# ReflowOvenController.net
KiCad netlist of a schematic drawn in EAGLE
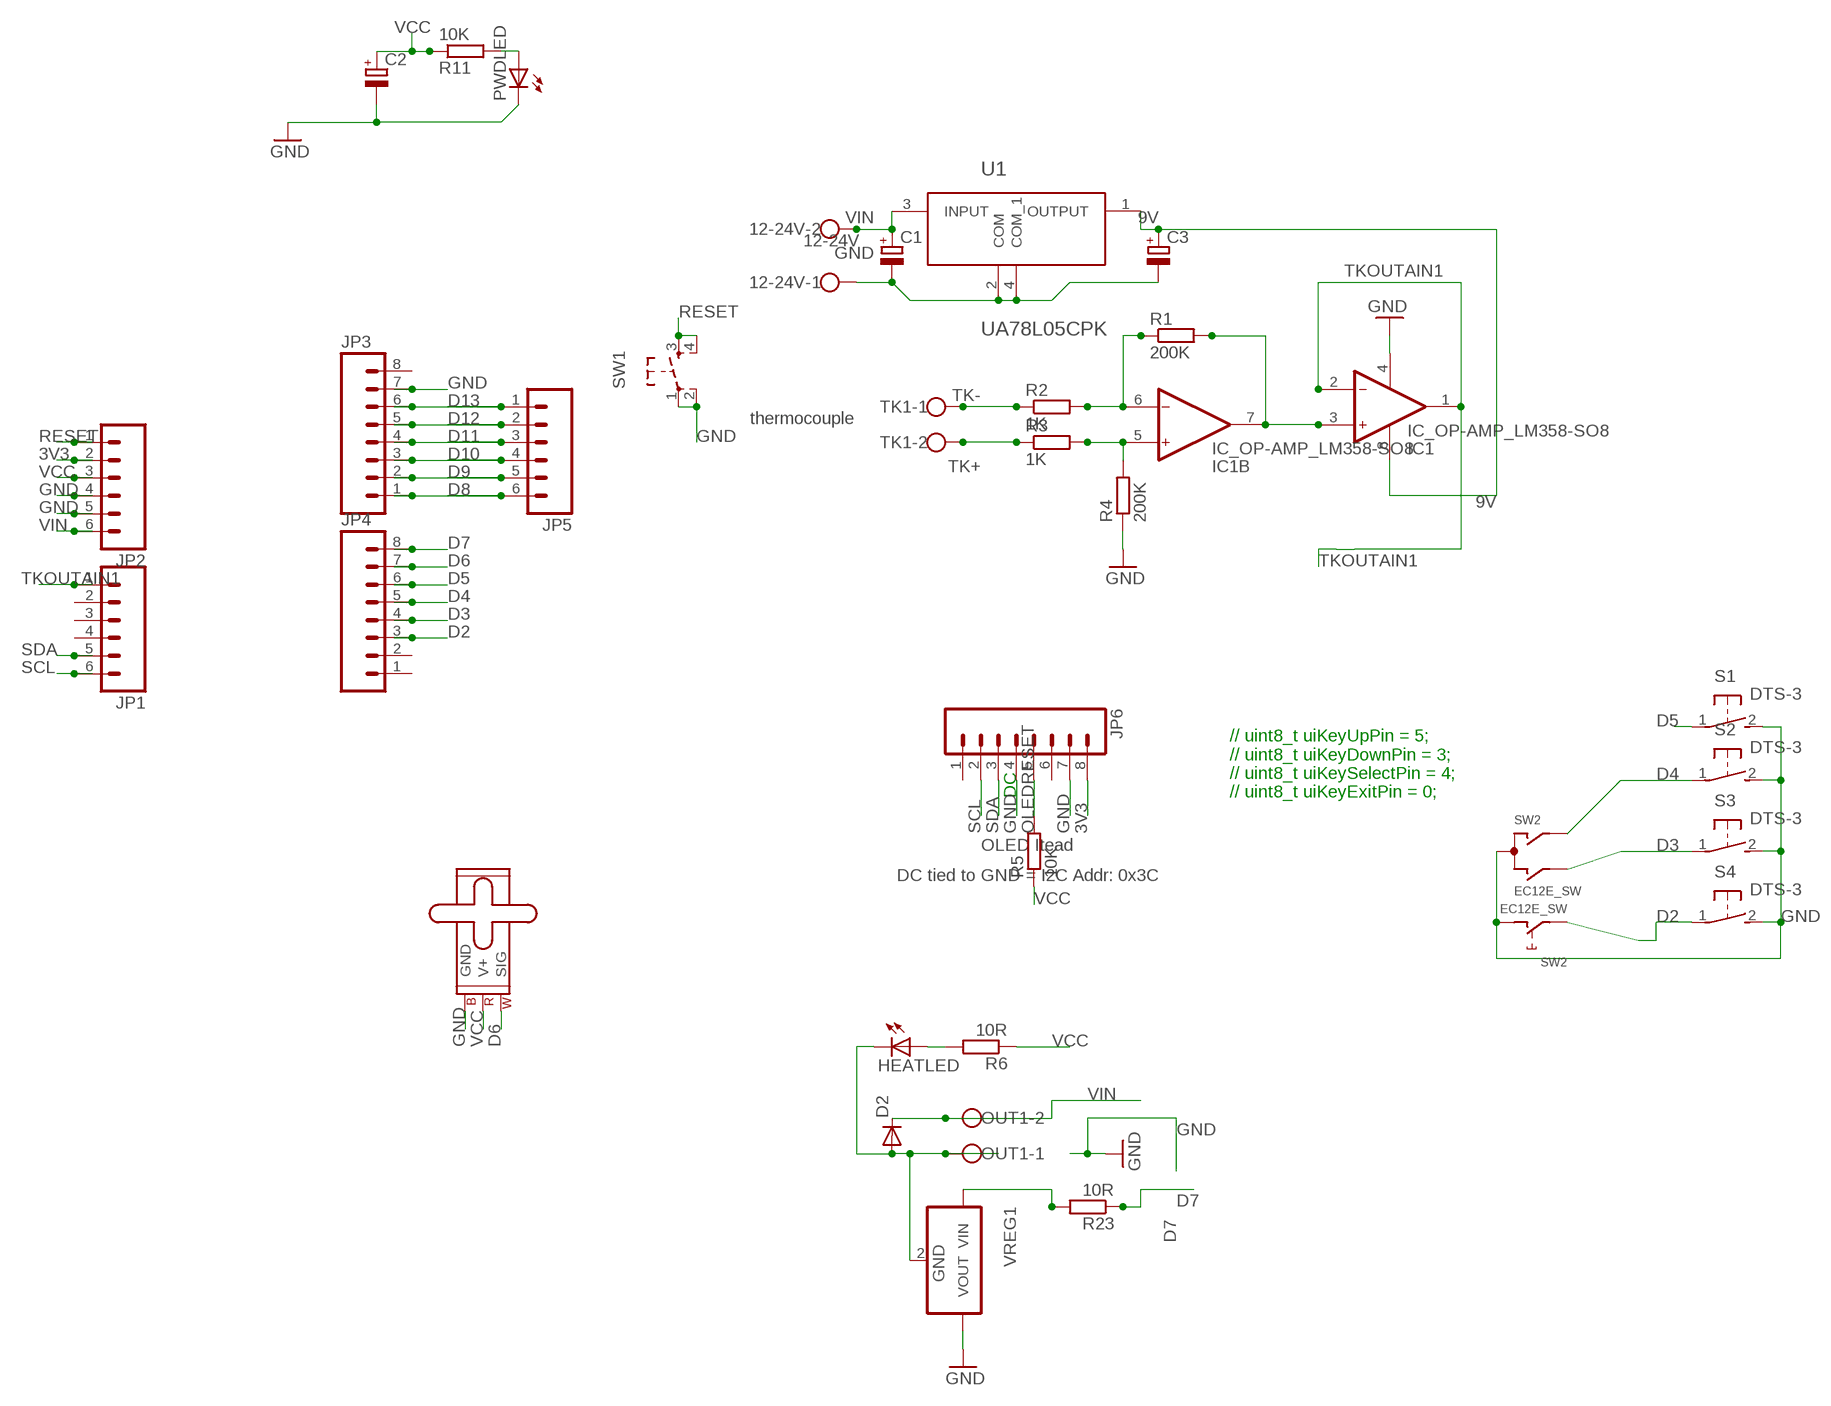
[diagram p0: schematic, sheet 1]

(export (version "E")
  (design (tool "Eeschema 10.0.6"))
  (components
    (comp (ref "12-24V")
      (value "W237-102")
      (footprint "eagle-import:W237-102")
      (fields (field (name "MPN") "237-102"))
      (libsource (lib "eagle-import") (part "W237-102"))
    )
    (comp (ref "C1")
      (value "CPOL-EU153CLV-0505")
      (footprint "eagle-import:153CLV-0505")
      (libsource (lib "eagle-import") (part "CPOL-EU153CLV-0505"))
    )
    (comp (ref "C2")
      (value "CPOL-EU153CLV-0505")
      (footprint "eagle-import:153CLV-0505")
      (libsource (lib "eagle-import") (part "CPOL-EU153CLV-0505"))
    )
    (comp (ref "C3")
      (value "CPOL-EU153CLV-0505")
      (footprint "eagle-import:153CLV-0505")
      (libsource (lib "eagle-import") (part "CPOL-EU153CLV-0505"))
    )
    (comp (ref "D2")
      (value "DIODESMA-ALT")
      (footprint "eagle-import:SMA-DIODE_ALT")
      (libsource (lib "eagle-import") (part "DIODESMA-ALT"))
    )
    (comp (ref "HEATLED")
      (value "LEDCHIPLED_1206")
      (footprint "eagle-import:CHIPLED_1206")
      (libsource (lib "eagle-import") (part "LEDCHIPLED_1206"))
    )
    (comp (ref "IC1")
      (value "IC_OP-AMP_LM358-SO8")
      (footprint "eagle-import:SO-8")
      (libsource (lib "eagle-import") (part "IC_OP-AMP_LM358-SO8"))
    )
    (comp (ref "JP1")
      (value "M06LOCK_LONGPADS")
      (footprint "eagle-import:1X06_LOCK_LONGPADS")
      (libsource (lib "eagle-import") (part "M06LOCK_LONGPADS"))
    )
    (comp (ref "JP2")
      (value "M06LOCK_LONGPADS")
      (footprint "eagle-import:1X06_LOCK_LONGPADS")
      (libsource (lib "eagle-import") (part "M06LOCK_LONGPADS"))
    )
    (comp (ref "JP3")
      (value "M08LOCK_LONGPADS")
      (footprint "eagle-import:1X08_LOCK_LONGPADS")
      (libsource (lib "eagle-import") (part "M08LOCK_LONGPADS"))
    )
    (comp (ref "JP4")
      (value "M08LOCK_LONGPADS")
      (footprint "eagle-import:1X08_LOCK_LONGPADS")
      (libsource (lib "eagle-import") (part "M08LOCK_LONGPADS"))
    )
    (comp (ref "JP5")
      (value "M06LOCK_LONGPADS")
      (footprint "eagle-import:1X06_LOCK_LONGPADS")
      (libsource (lib "eagle-import") (part "M06LOCK_LONGPADS"))
    )
    (comp (ref "JP6")
      (value "M08LOCK")
      (footprint "eagle-import:1X08_LOCK")
      (libsource (lib "eagle-import") (part "M08LOCK"))
    )
    (comp (ref "OUT1")
      (value "W237-102")
      (footprint "eagle-import:W237-102")
      (fields (field (name "MPN") "237-102"))
      (libsource (lib "eagle-import") (part "W237-102"))
    )
    (comp (ref "PWDLED")
      (value "LEDCHIPLED_1206")
      (footprint "eagle-import:CHIPLED_1206")
      (libsource (lib "eagle-import") (part "LEDCHIPLED_1206"))
    )
    (comp (ref "R1")
      (value "200K")
      (footprint "eagle-import:M1206")
      (libsource (lib "eagle-import") (part "R-EU_M1206"))
    )
    (comp (ref "R2")
      (value "1K")
      (footprint "eagle-import:M1206")
      (libsource (lib "eagle-import") (part "R-EU_M1206"))
    )
    (comp (ref "R3")
      (value "1K")
      (footprint "eagle-import:M1206")
      (libsource (lib "eagle-import") (part "R-EU_M1206"))
    )
    (comp (ref "R4")
      (value "200K")
      (footprint "eagle-import:M1206")
      (libsource (lib "eagle-import") (part "R-EU_M1206"))
    )
    (comp (ref "R5")
      (value "10K")
      (footprint "eagle-import:R1206")
      (libsource (lib "eagle-import") (part "RESISTOR-1206"))
    )
    (comp (ref "R6")
      (value "10R")
      (footprint "eagle-import:M1206")
      (libsource (lib "eagle-import") (part "R-EU_M1206"))
    )
    (comp (ref "R11")
      (value "10K")
      (footprint "eagle-import:R1206")
      (libsource (lib "eagle-import") (part "RESISTOR-1206"))
    )
    (comp (ref "R23")
      (value "10R")
      (footprint "eagle-import:M1206")
      (libsource (lib "eagle-import") (part "R-EU_M1206"))
    )
    (comp (ref "S1")
      (value "DTS-3")
      (footprint "eagle-import:DTS-3")
      (libsource (lib "eagle-import") (part "DTS-3"))
    )
    (comp (ref "S2")
      (value "DTS-3")
      (footprint "eagle-import:DTS-3")
      (libsource (lib "eagle-import") (part "DTS-3"))
    )
    (comp (ref "S3")
      (value "DTS-3")
      (footprint "eagle-import:DTS-3")
      (libsource (lib "eagle-import") (part "DTS-3"))
    )
    (comp (ref "S4")
      (value "DTS-3")
      (footprint "eagle-import:DTS-3")
      (libsource (lib "eagle-import") (part "DTS-3"))
    )
    (comp (ref "SERVO")
      (value "SMALL_SERVO")
      (footprint "eagle-import:1X03")
      (libsource (lib "eagle-import") (part "SMALL_SERVO"))
    )
    (comp (ref "SW1")
      (value "SW_TACT_4P")
      (footprint "eagle-import:SW_TACT_SMALL")
      (libsource (lib "eagle-import") (part "SW_TACT_4P"))
    )
    (comp (ref "SW2")
      (value "EC12E_SW")
      (footprint "eagle-import:ALPS_EC12E_SW")
      (fields (field (name "MPN") "EC12E2424407"))
      (libsource (lib "eagle-import") (part "EC12E_SW"))
    )
    (comp (ref "TK1")
      (value "W237-102")
      (footprint "eagle-import:W237-102")
      (fields (field (name "MPN") "237-102"))
      (libsource (lib "eagle-import") (part "W237-102"))
    )
    (comp (ref "U1")
      (value "UA78L05CPK")
      (footprint "eagle-import:SOT150P400X160-4N")
      (libsource (lib "eagle-import") (part "UA78L05CPK"))
    )
    (comp (ref "VREG1")
      (value "VREG_3PINS-D2PAK")
      (footprint "eagle-import:D2PAK")
      (libsource (lib "eagle-import") (part "VREG_3PINS-D2PAK"))
    )
  )
  (nets
    (net (code "1") (name "/3V3") (class "Default")
      (node (ref "JP2") (pin "2") (pinfunction "2_2") (pintype "passive"))
      (node (ref "JP6") (pin "8") (pinfunction "8_8") (pintype "passive"))
    )
    (net (code "2") (name "/9V") (class "Default")
      (node (ref "C3") (pin "+") (pinfunction "+_+") (pintype "passive"))
      (node (ref "IC1") (pin "8") (pinfunction "V+_8") (pintype "power_in"))
      (node (ref "U1") (pin "1") (pinfunction "OUTPUT_1") (pintype "output"))
    )
    (net (code "3") (name "/D2") (class "Default")
      (node (ref "JP4") (pin "3") (pinfunction "3_3") (pintype "passive"))
      (node (ref "S4") (pin "1") (pinfunction "1_1") (pintype "passive"))
      (node (ref "SW2") (pin "E") (pinfunction "2_E") (pintype "passive"))
    )
    (net (code "4") (name "/D3") (class "Default")
      (node (ref "JP4") (pin "4") (pinfunction "4_4") (pintype "passive"))
      (node (ref "S3") (pin "1") (pinfunction "1_1") (pintype "passive"))
      (node (ref "SW2") (pin "B") (pinfunction "B_B") (pintype "passive"))
    )
    (net (code "5") (name "/D4") (class "Default")
      (node (ref "JP4") (pin "5") (pinfunction "5_5") (pintype "passive"))
      (node (ref "S2") (pin "1") (pinfunction "1_1") (pintype "passive"))
      (node (ref "SW2") (pin "A") (pinfunction "A_A") (pintype "passive"))
    )
    (net (code "6") (name "/D5") (class "Default")
      (node (ref "JP4") (pin "6") (pinfunction "6_6") (pintype "passive"))
      (node (ref "S1") (pin "1") (pinfunction "1_1") (pintype "passive"))
    )
    (net (code "7") (name "/D6") (class "Default")
      (node (ref "JP4") (pin "7") (pinfunction "7_7") (pintype "passive"))
      (node (ref "SERVO") (pin "1") (pinfunction "SIG_1") (pintype "bidirectional"))
    )
    (net (code "8") (name "/D7") (class "Default")
      (node (ref "JP4") (pin "8") (pinfunction "8_8") (pintype "passive"))
      (node (ref "R23") (pin "1") (pinfunction "1_1") (pintype "passive"))
    )
    (net (code "9") (name "/D8") (class "Default")
      (node (ref "JP3") (pin "1") (pinfunction "1_1") (pintype "passive"))
      (node (ref "JP5") (pin "6") (pinfunction "6_6") (pintype "passive"))
    )
    (net (code "10") (name "/D9") (class "Default")
      (node (ref "JP3") (pin "2") (pinfunction "2_2") (pintype "passive"))
      (node (ref "JP5") (pin "5") (pinfunction "5_5") (pintype "passive"))
    )
    (net (code "11") (name "/D10") (class "Default")
      (node (ref "JP3") (pin "3") (pinfunction "3_3") (pintype "passive"))
      (node (ref "JP5") (pin "4") (pinfunction "4_4") (pintype "passive"))
    )
    (net (code "12") (name "/D11") (class "Default")
      (node (ref "JP3") (pin "4") (pinfunction "4_4") (pintype "passive"))
      (node (ref "JP5") (pin "3") (pinfunction "3_3") (pintype "passive"))
    )
    (net (code "13") (name "/D12") (class "Default")
      (node (ref "JP3") (pin "5") (pinfunction "5_5") (pintype "passive"))
      (node (ref "JP5") (pin "2") (pinfunction "2_2") (pintype "passive"))
    )
    (net (code "14") (name "/D13") (class "Default")
      (node (ref "JP3") (pin "6") (pinfunction "6_6") (pintype "passive"))
      (node (ref "JP5") (pin "1") (pinfunction "1_1") (pintype "passive"))
    )
    (net (code "15") (name "/OLEDRESET") (class "Default")
      (node (ref "JP6") (pin "5") (pinfunction "5_5") (pintype "passive"))
      (node (ref "R5") (pin "2") (pinfunction "2_2") (pintype "passive"))
    )
    (net (code "16") (name "/RESET") (class "Default")
      (node (ref "JP2") (pin "1") (pinfunction "1_1") (pintype "passive"))
      (node (ref "SW1") (pin "3") (pinfunction "3_3") (pintype "passive"))
      (node (ref "SW1") (pin "4") (pinfunction "4_4") (pintype "passive"))
    )
    (net (code "17") (name "/SCL") (class "Default")
      (node (ref "JP1") (pin "6") (pinfunction "6_6") (pintype "passive"))
      (node (ref "JP6") (pin "2") (pinfunction "2_2") (pintype "passive"))
    )
    (net (code "18") (name "/SDA") (class "Default")
      (node (ref "JP1") (pin "5") (pinfunction "5_5") (pintype "passive"))
      (node (ref "JP6") (pin "3") (pinfunction "3_3") (pintype "passive"))
    )
    (net (code "19") (name "/TK+") (class "Default")
      (node (ref "R3") (pin "1") (pinfunction "1_1") (pintype "passive"))
      (node (ref "TK1") (pin "2") (pinfunction "KL_2") (pintype "passive"))
    )
    (net (code "20") (name "/TK-") (class "Default")
      (node (ref "R2") (pin "1") (pinfunction "1_1") (pintype "passive"))
      (node (ref "TK1") (pin "1") (pinfunction "KL_1") (pintype "passive"))
    )
    (net (code "21") (name "/TKOUTAIN1") (class "Default")
      (node (ref "IC1") (pin "1") (pinfunction "OUT_1") (pintype "output"))
      (node (ref "IC1") (pin "2") (pinfunction "-_2") (pintype "input"))
      (node (ref "JP1") (pin "1") (pinfunction "1_1") (pintype "passive"))
    )
    (net (code "22") (name "/VCC") (class "Default")
      (node (ref "C2") (pin "+") (pinfunction "+_+") (pintype "passive"))
      (node (ref "JP2") (pin "3") (pinfunction "3_3") (pintype "passive"))
      (node (ref "R11") (pin "1") (pinfunction "1_1") (pintype "passive"))
      (node (ref "R5") (pin "1") (pinfunction "1_1") (pintype "passive"))
      (node (ref "R6") (pin "1") (pinfunction "1_1") (pintype "passive"))
      (node (ref "SERVO") (pin "2") (pinfunction "V+_2") (pintype "bidirectional"))
    )
    (net (code "23") (name "/VIN") (class "Default")
      (node (ref "12-24V") (pin "2") (pinfunction "KL_2") (pintype "passive"))
      (node (ref "C1") (pin "+") (pinfunction "+_+") (pintype "passive"))
      (node (ref "D2") (pin "C") (pinfunction "C_C") (pintype "passive"))
      (node (ref "JP2") (pin "6") (pinfunction "6_6") (pintype "passive"))
      (node (ref "OUT1") (pin "2") (pinfunction "KL_2") (pintype "passive"))
      (node (ref "U1") (pin "3") (pinfunction "INPUT_3") (pintype "input"))
    )
    (net (code "24") (name "GND") (class "Default")
      (node (ref "12-24V") (pin "1") (pinfunction "KL_1") (pintype "passive"))
      (node (ref "C1") (pin "-") (pinfunction "-_-") (pintype "passive"))
      (node (ref "C2") (pin "-") (pinfunction "-_-") (pintype "passive"))
      (node (ref "C3") (pin "-") (pinfunction "-_-") (pintype "passive"))
      (node (ref "IC1") (pin "4") (pinfunction "V-_4") (pintype "power_in"))
      (node (ref "JP2") (pin "4") (pinfunction "4_4") (pintype "passive"))
      (node (ref "JP2") (pin "5") (pinfunction "5_5") (pintype "passive"))
      (node (ref "JP3") (pin "7") (pinfunction "7_7") (pintype "passive"))
      (node (ref "JP6") (pin "4") (pinfunction "4_4") (pintype "passive"))
      (node (ref "JP6") (pin "7") (pinfunction "7_7") (pintype "passive"))
      (node (ref "PWDLED") (pin "C") (pinfunction "C_C") (pintype "passive"))
      (node (ref "R4") (pin "1") (pinfunction "1_1") (pintype "passive"))
      (node (ref "S1") (pin "2") (pinfunction "2_2") (pintype "passive"))
      (node (ref "S2") (pin "2") (pinfunction "2_2") (pintype "passive"))
      (node (ref "S3") (pin "2") (pinfunction "2_2") (pintype "passive"))
      (node (ref "S4") (pin "2") (pinfunction "2_2") (pintype "passive"))
      (node (ref "SERVO") (pin "3") (pinfunction "GND_3") (pintype "bidirectional"))
      (node (ref "SW1") (pin "1") (pinfunction "1_1") (pintype "passive"))
      (node (ref "SW1") (pin "2") (pinfunction "2_2") (pintype "passive"))
      (node (ref "SW2") (pin "C") (pinfunction "C_C") (pintype "passive"))
      (node (ref "SW2") (pin "D") (pinfunction "1_D") (pintype "passive"))
      (node (ref "U1") (pin "2") (pinfunction "COM_2") (pintype "power_in"))
      (node (ref "U1") (pin "4") (pinfunction "COM_1_4") (pintype "power_in"))
      (node (ref "VREG1") (pin "3") (pinfunction "VOUT_3") (pintype "bidirectional"))
    )
    (net (code "25") (name "Net-(HEATLED-PadA)") (class "Default")
      (node (ref "HEATLED") (pin "A") (pinfunction "A_A") (pintype "passive"))
      (node (ref "R6") (pin "2") (pinfunction "2_2") (pintype "passive"))
    )
    (net (code "26") (name "Net-(IC1A-+)") (class "Default")
      (node (ref "IC1") (pin "3") (pinfunction "+_3") (pintype "input"))
      (node (ref "IC1") (pin "7") (pinfunction "OUT_7") (pintype "output"))
      (node (ref "R1") (pin "2") (pinfunction "2_2") (pintype "passive"))
    )
    (net (code "27") (name "Net-(IC1B-+)") (class "Default")
      (node (ref "IC1") (pin "5") (pinfunction "+_5") (pintype "input"))
      (node (ref "R3") (pin "2") (pinfunction "2_2") (pintype "passive"))
      (node (ref "R4") (pin "2") (pinfunction "2_2") (pintype "passive"))
    )
    (net (code "28") (name "Net-(IC1B--)") (class "Default")
      (node (ref "IC1") (pin "6") (pinfunction "-_6") (pintype "input"))
      (node (ref "R1") (pin "1") (pinfunction "1_1") (pintype "passive"))
      (node (ref "R2") (pin "2") (pinfunction "2_2") (pintype "passive"))
    )
    (net (code "29") (name "Net-(OUT1A-KL)") (class "Default")
      (node (ref "D2") (pin "A") (pinfunction "A_A") (pintype "passive"))
      (node (ref "HEATLED") (pin "C") (pinfunction "C_C") (pintype "passive"))
      (node (ref "OUT1") (pin "1") (pinfunction "KL_1") (pintype "passive"))
      (node (ref "VREG1") (pin "2") (pinfunction "GND_2") (pintype "bidirectional"))
    )
    (net (code "30") (name "Net-(PWDLED-PadA)") (class "Default")
      (node (ref "PWDLED") (pin "A") (pinfunction "A_A") (pintype "passive"))
      (node (ref "R11") (pin "2") (pinfunction "2_2") (pintype "passive"))
    )
    (net (code "31") (name "Net-(VREG1-VIN)") (class "Default")
      (node (ref "R23") (pin "2") (pinfunction "2_2") (pintype "passive"))
      (node (ref "VREG1") (pin "1") (pinfunction "VIN_1") (pintype "bidirectional"))
    )
    (net (code "32") (name "unconnected-(JP1-Pad2)") (class "Default")
      (node (ref "JP1") (pin "2") (pinfunction "2_2") (pintype "passive"))
    )
    (net (code "33") (name "unconnected-(JP1-Pad3)") (class "Default")
      (node (ref "JP1") (pin "3") (pinfunction "3_3") (pintype "passive"))
    )
    (net (code "34") (name "unconnected-(JP1-Pad4)") (class "Default")
      (node (ref "JP1") (pin "4") (pinfunction "4_4") (pintype "passive"))
    )
    (net (code "35") (name "unconnected-(JP3-Pad8)") (class "Default")
      (node (ref "JP3") (pin "8") (pinfunction "8_8") (pintype "passive"))
    )
    (net (code "36") (name "unconnected-(JP4-Pad1)") (class "Default")
      (node (ref "JP4") (pin "1") (pinfunction "1_1") (pintype "passive"))
    )
    (net (code "37") (name "unconnected-(JP4-Pad2)") (class "Default")
      (node (ref "JP4") (pin "2") (pinfunction "2_2") (pintype "passive"))
    )
    (net (code "38") (name "unconnected-(JP6-Pad1)") (class "Default")
      (node (ref "JP6") (pin "1") (pinfunction "1_1") (pintype "passive"))
    )
    (net (code "39") (name "unconnected-(JP6-Pad6)") (class "Default")
      (node (ref "JP6") (pin "6") (pinfunction "6_6") (pintype "passive"))
    )
  )
)
